# max31865_breakout.net
KiCad netlist of a schematic drawn in EAGLE
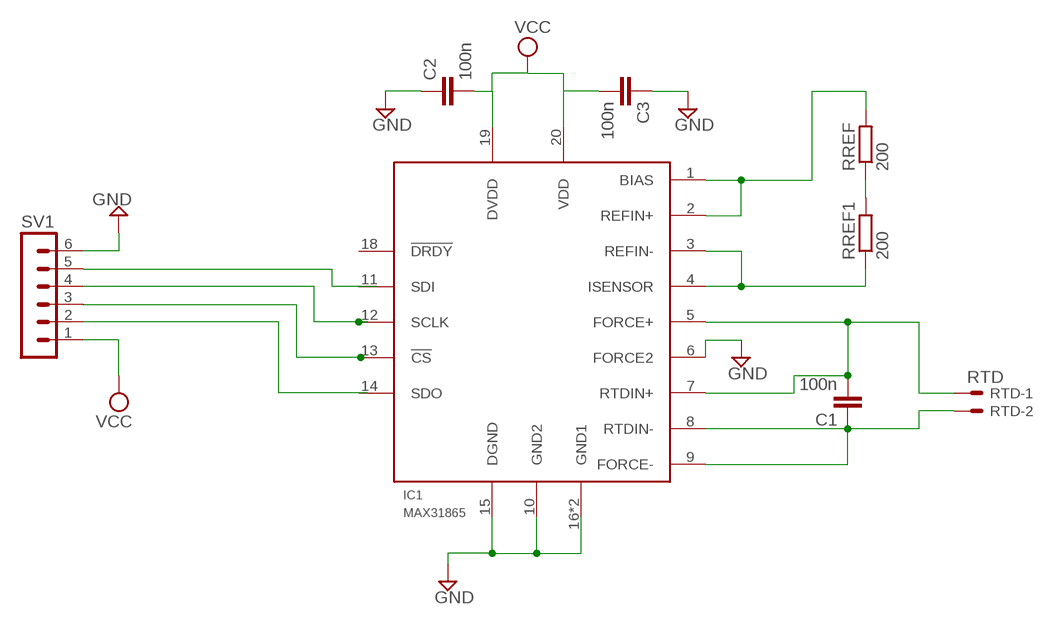
[diagram p0: schematic, sheet 1]

(export (version "E")
  (design (tool "Eeschema 10.0.6"))
  (components
    (comp (ref "C1")
      (value "100n")
      (footprint "eagle-import:C0805K")
      (libsource (lib "eagle-import") (part "C-EUC0805K"))
    )
    (comp (ref "C2")
      (value "100n")
      (footprint "eagle-import:C0805K")
      (libsource (lib "eagle-import") (part "C-EUC0805K"))
    )
    (comp (ref "C3")
      (value "100n")
      (footprint "eagle-import:C0805K")
      (libsource (lib "eagle-import") (part "C-EUC0805K"))
    )
    (comp (ref "IC1")
      (value "MAX31865")
      (footprint "eagle-import:TQFN20-5X5")
      (libsource (lib "eagle-import") (part "MAX31865"))
    )
    (comp (ref "RREF")
      (value "200")
      (footprint "eagle-import:M1206")
      (libsource (lib "eagle-import") (part "R-EU_M1206"))
    )
    (comp (ref "RREF1")
      (value "200")
      (footprint "eagle-import:M1206")
      (libsource (lib "eagle-import") (part "R-EU_M1206"))
    )
    (comp (ref "RTD")
      (value "RTD")
      (footprint "eagle-import:22-23-2021")
      (fields (field (name "MF") "MOLEX") (field (name "MPN") "22-23-2021"))
      (libsource (lib "eagle-import") (part "22-23-2021"))
    )
    (comp (ref "SV1")
      (value "MA06-1")
      (footprint "eagle-import:MA06-1")
      (libsource (lib "eagle-import") (part "MA06-1"))
    )
  )
  (nets
    (net (code "1") (name "GND") (class "Default")
      (node (ref "C2") (pin "1") (pinfunction "1_1") (pintype "passive"))
      (node (ref "C3") (pin "1") (pinfunction "1_1") (pintype "passive"))
      (node (ref "IC1") (pin "10") (pinfunction "GND2_10") (pintype "power_in"))
      (node (ref "IC1") (pin "15") (pinfunction "DGND_15") (pintype "power_in"))
      (node (ref "IC1") (pin "16") (pinfunction "GND1_16") (pintype "power_in"))
      (node (ref "IC1") (pin "6") (pinfunction "FORCE2_6") (pintype "input"))
      (node (ref "IC1") (pin "EXP") (pinfunction "GND1_EXP") (pintype "power_in"))
      (node (ref "SV1") (pin "6") (pinfunction "6_6") (pintype "passive"))
    )
    (net (code "2") (name "Net-(IC1-BIAS)") (class "Default")
      (node (ref "IC1") (pin "1") (pinfunction "BIAS_1") (pintype "input"))
      (node (ref "IC1") (pin "2") (pinfunction "REFIN+_2") (pintype "input"))
      (node (ref "RREF") (pin "2") (pinfunction "2_2") (pintype "passive"))
    )
    (net (code "3") (name "Net-(IC1-FORCE+)") (class "Default")
      (node (ref "C1") (pin "2") (pinfunction "2_2") (pintype "passive"))
      (node (ref "IC1") (pin "5") (pinfunction "FORCE+_5") (pintype "input"))
      (node (ref "IC1") (pin "7") (pinfunction "RTDIN+_7") (pintype "input"))
      (node (ref "RTD") (pin "1") (pinfunction "S_1") (pintype "passive"))
    )
    (net (code "4") (name "Net-(IC1-FORCE-)") (class "Default")
      (node (ref "C1") (pin "1") (pinfunction "1_1") (pintype "passive"))
      (node (ref "IC1") (pin "8") (pinfunction "RTDIN-_8") (pintype "input"))
      (node (ref "IC1") (pin "9") (pinfunction "FORCE-_9") (pintype "input"))
      (node (ref "RTD") (pin "2") (pinfunction "S_2") (pintype "passive"))
    )
    (net (code "5") (name "Net-(IC1-ISENSOR)") (class "Default")
      (node (ref "IC1") (pin "3") (pinfunction "REFIN-_3") (pintype "input"))
      (node (ref "IC1") (pin "4") (pinfunction "ISENSOR_4") (pintype "input"))
      (node (ref "RREF1") (pin "1") (pinfunction "1_1") (pintype "passive"))
    )
    (net (code "6") (name "Net-(IC1-SCLK)") (class "Default")
      (node (ref "IC1") (pin "12") (pinfunction "SCLK_12") (pintype "input"))
      (node (ref "SV1") (pin "4") (pinfunction "4_4") (pintype "passive"))
    )
    (net (code "7") (name "Net-(RREF-Pad1)") (class "Default")
      (node (ref "RREF") (pin "1") (pinfunction "1_1") (pintype "passive"))
      (node (ref "RREF1") (pin "2") (pinfunction "2_2") (pintype "passive"))
    )
    (net (code "8") (name "VCC") (class "Default")
      (node (ref "C2") (pin "2") (pinfunction "2_2") (pintype "passive"))
      (node (ref "C3") (pin "2") (pinfunction "2_2") (pintype "passive"))
      (node (ref "IC1") (pin "19") (pinfunction "DVDD_19") (pintype "power_in"))
      (node (ref "IC1") (pin "20") (pinfunction "VDD_20") (pintype "power_in"))
      (node (ref "SV1") (pin "1") (pinfunction "1_1") (pintype "passive"))
    )
    (net (code "9") (name "unconnected-(IC1-SDI-Pad11)") (class "Default")
      (node (ref "IC1") (pin "11") (pinfunction "SDI_11") (pintype "input"))
    )
    (net (code "10") (name "unconnected-(IC1-SDO-Pad14)") (class "Default")
      (node (ref "IC1") (pin "14") (pinfunction "SDO_14") (pintype "output"))
    )
    (net (code "11") (name "unconnected-(IC1-~{CS}-Pad13)") (class "Default")
      (node (ref "IC1") (pin "13") (pinfunction "~{CS}_13") (pintype "input"))
    )
    (net (code "12") (name "unconnected-(IC1-~{DRDY}-Pad18)") (class "Default")
      (node (ref "IC1") (pin "18") (pinfunction "~{DRDY}_18") (pintype "output"))
    )
    (net (code "13") (name "unconnected-(SV1-Pad2)") (class "Default")
      (node (ref "SV1") (pin "2") (pinfunction "2_2") (pintype "passive"))
    )
    (net (code "14") (name "unconnected-(SV1-Pad3)") (class "Default")
      (node (ref "SV1") (pin "3") (pinfunction "3_3") (pintype "passive"))
    )
    (net (code "15") (name "unconnected-(SV1-Pad5)") (class "Default")
      (node (ref "SV1") (pin "5") (pinfunction "5_5") (pintype "passive"))
    )
  )
)
